# Power_and_Regulator.net
KiCad netlist of a schematic drawn in Altium Designer
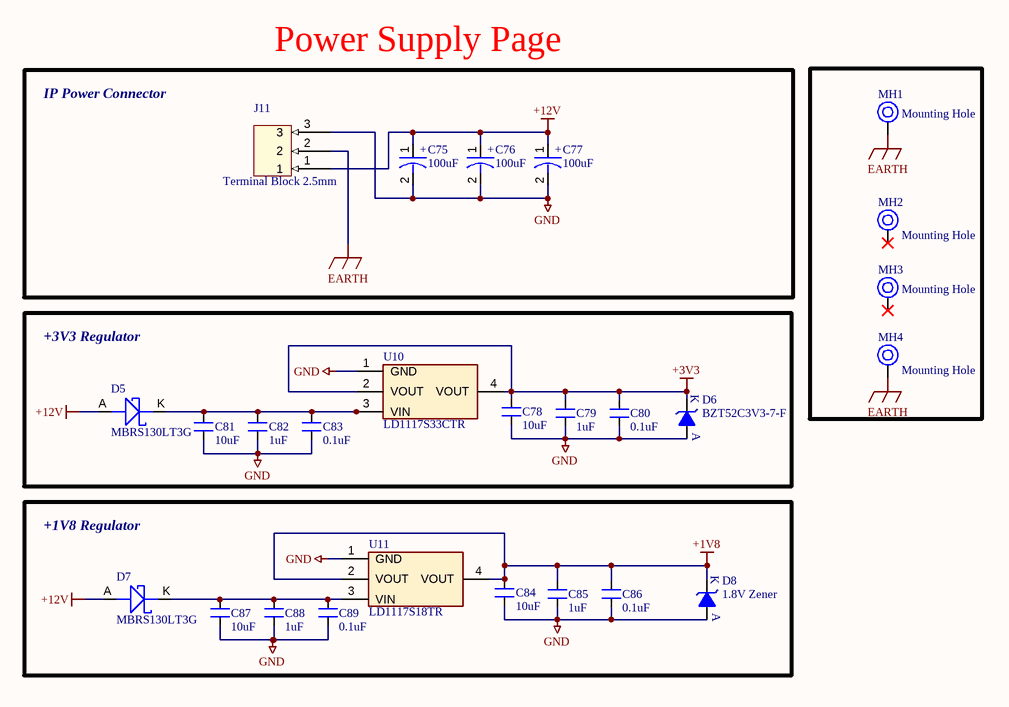
[diagram p0: Power and Regulator.SchDoc]

(export (version "E")
  (design (tool "Eeschema 10.0.6"))
  (components
    (comp (ref "C75")
      (value "100uF")
      (footprint "ACAP_P305_D393_H393_RAD")
      (description "100µF 50V Aluminum Polymer Capacitor Radial, Can - SMD 28mOhm 4000 Hrs @ 125°C")
      (fields
        (field (name "MANUFACTURER") "Nichicon")
        (field (name "MANUFACTURER PART NUMBER") "GYA1H101MCQ1GS")
      )
      (libsource (lib "ESTEEMPCBLIB") (part "CAP-P_100uF-50V-20%-RAD"))
    )
    (comp (ref "C76")
      (value "100uF")
      (footprint "ACAP_P305_D393_H393_RAD")
      (description "100µF 50V Aluminum Polymer Capacitor Radial, Can - SMD 28mOhm 4000 Hrs @ 125°C")
      (fields
        (field (name "MANUFACTURER") "Nichicon")
        (field (name "MANUFACTURER PART NUMBER") "GYA1H101MCQ1GS")
      )
      (libsource (lib "ESTEEMPCBLIB") (part "CAP-P_100uF-50V-20%-RAD"))
    )
    (comp (ref "C77")
      (value "100uF")
      (footprint "ACAP_P305_D393_H393_RAD")
      (description "100µF 50V Aluminum Polymer Capacitor Radial, Can - SMD 28mOhm 4000 Hrs @ 125°C")
      (fields
        (field (name "MANUFACTURER") "Nichicon")
        (field (name "MANUFACTURER PART NUMBER") "GYA1H101MCQ1GS")
      )
      (libsource (lib "ESTEEMPCBLIB") (part "CAP-P_100uF-50V-20%-RAD"))
    )
    (comp (ref "C78")
      (value "10uF")
      (footprint "CAP_1206")
      (description "10µF ±10% 50V Ceramic Capacitor X7R 1206 (3216 Metric)")
      (fields
        (field (name "MANUFACTURER") "KEMET")
        (field (name "MANUFACTURER PART NUMBER") "CL31B106KBHNNNE")
      )
      (libsource (lib "ESTEEMPCBLIB") (part "CAP_10uF-50V-10%-1206"))
    )
    (comp (ref "C79")
      (value "1uF")
      (footprint "CAP_0805")
      (description "1µF ±5% 50V Ceramic Capacitor X7R 0805 (2012 Metric)")
      (fields
        (field (name "MANUFACTURER") "Samsung")
        (field (name "MANUFACTURER PART NUMBER") "CC0805JKX7R9BB105")
      )
      (libsource (lib "ESTEEMPCBLIB") (part "CAP_1uF-50V-5%-0805"))
    )
    (comp (ref "C80")
      (value "0.1uF")
      (footprint "CAP_0805")
      (description "0.1µF ±20% 50V Ceramic Capacitor X7R 0805 (2012 Metric)")
      (fields
        (field (name "MANUFACTURER") "Samsung Electro-Mechanics")
        (field (name "MANUFACTURER PART NUMBER") "CL21B104MBCNNNC")
      )
      (libsource (lib "ESTEEMPCBLIB") (part "CAP_0.1uF-50V-20%-0805"))
    )
    (comp (ref "C81")
      (value "10uF")
      (footprint "CAP_1206")
      (description "10µF ±10% 50V Ceramic Capacitor X7R 1206 (3216 Metric)")
      (fields
        (field (name "MANUFACTURER") "KEMET")
        (field (name "MANUFACTURER PART NUMBER") "CL31B106KBHNNNE")
      )
      (libsource (lib "ESTEEMPCBLIB") (part "CAP_10uF-50V-10%-1206"))
    )
    (comp (ref "C82")
      (value "1uF")
      (footprint "CAP_0805")
      (description "1µF ±5% 50V Ceramic Capacitor X7R 0805 (2012 Metric)")
      (fields
        (field (name "MANUFACTURER") "Samsung")
        (field (name "MANUFACTURER PART NUMBER") "CC0805JKX7R9BB105")
      )
      (libsource (lib "ESTEEMPCBLIB") (part "CAP_1uF-50V-5%-0805"))
    )
    (comp (ref "C83")
      (value "0.1uF")
      (footprint "CAP_0805")
      (description "0.1µF ±20% 50V Ceramic Capacitor X7R 0805 (2012 Metric)")
      (fields
        (field (name "MANUFACTURER") "Samsung Electro-Mechanics")
        (field (name "MANUFACTURER PART NUMBER") "CL21B104MBCNNNC")
      )
      (libsource (lib "ESTEEMPCBLIB") (part "CAP_0.1uF-50V-20%-0805"))
    )
    (comp (ref "C84")
      (value "10uF")
      (footprint "CAP_1206")
      (description "10µF ±10% 50V Ceramic Capacitor X7R 1206 (3216 Metric)")
      (fields
        (field (name "MANUFACTURER") "KEMET")
        (field (name "MANUFACTURER PART NUMBER") "CL31B106KBHNNNE")
      )
      (libsource (lib "ESTEEMPCBLIB") (part "CAP_10uF-50V-10%-1206"))
    )
    (comp (ref "C85")
      (value "1uF")
      (footprint "CAP_0805")
      (description "1µF ±5% 50V Ceramic Capacitor X7R 0805 (2012 Metric)")
      (fields
        (field (name "MANUFACTURER") "Samsung")
        (field (name "MANUFACTURER PART NUMBER") "CC0805JKX7R9BB105")
      )
      (libsource (lib "ESTEEMPCBLIB") (part "CAP_1uF-50V-5%-0805"))
    )
    (comp (ref "C86")
      (value "0.1uF")
      (footprint "CAP_0805")
      (description "0.1µF ±20% 50V Ceramic Capacitor X7R 0805 (2012 Metric)")
      (fields
        (field (name "MANUFACTURER") "Samsung Electro-Mechanics")
        (field (name "MANUFACTURER PART NUMBER") "CL21B104MBCNNNC")
      )
      (libsource (lib "ESTEEMPCBLIB") (part "CAP_0.1uF-50V-20%-0805"))
    )
    (comp (ref "C87")
      (value "10uF")
      (footprint "CAP_1206")
      (description "10µF ±10% 50V Ceramic Capacitor X7R 1206 (3216 Metric)")
      (fields
        (field (name "MANUFACTURER") "KEMET")
        (field (name "MANUFACTURER PART NUMBER") "CL31B106KBHNNNE")
      )
      (libsource (lib "ESTEEMPCBLIB") (part "CAP_10uF-50V-10%-1206"))
    )
    (comp (ref "C88")
      (value "1uF")
      (footprint "CAP_0805")
      (description "1µF ±5% 50V Ceramic Capacitor X7R 0805 (2012 Metric)")
      (fields
        (field (name "MANUFACTURER") "Samsung")
        (field (name "MANUFACTURER PART NUMBER") "CC0805JKX7R9BB105")
      )
      (libsource (lib "ESTEEMPCBLIB") (part "CAP_1uF-50V-5%-0805"))
    )
    (comp (ref "C89")
      (value "0.1uF")
      (footprint "CAP_0805")
      (description "0.1µF ±20% 50V Ceramic Capacitor X7R 0805 (2012 Metric)")
      (fields
        (field (name "MANUFACTURER") "Samsung Electro-Mechanics")
        (field (name "MANUFACTURER PART NUMBER") "CL21B104MBCNNNC")
      )
      (libsource (lib "ESTEEMPCBLIB") (part "CAP_0.1uF-50V-20%-0805"))
    )
    (comp (ref "D5")
      (value "MBRS130LT3G")
      (footprint "DIO_SMB_DO-214AA")
      (description "Diode Schottky 30V 2A Surface Mount SMB")
      (fields (field (name "MANUFACTURER") "ON Semiconductor"))
      (libsource (lib "ESTEEMPCBLIB") (part "DIO-S_445mV-30V-2A-SMB"))
    )
    (comp (ref "D6")
      (value "BZT52C3V3-7-F")
      (footprint "DIO_SOD-123")
      (description "Zener Diode 3.3V 500mW ±6% Surface Mount SOD-123")
      (fields (field (name "MANUFACTURER") "Diodes Incorporated"))
      (libsource (lib "ESTEEMPCBLIB") (part "DIO-Z_3.3V-500mW-SOD123"))
    )
    (comp (ref "D7")
      (value "MBRS130LT3G")
      (footprint "DIO_SMB_DO-214AA")
      (description "Diode Schottky 30V 2A Surface Mount SMB")
      (fields (field (name "MANUFACTURER") "ON Semiconductor"))
      (libsource (lib "ESTEEMPCBLIB") (part "DIO-S_445mV-30V-2A-SMB"))
    )
    (comp (ref "D8")
      (value "1.8V Zener")
      (footprint "DIO_DO-213AB_SMD")
      (description "Zener Diode 1.8V 500mW ±5% Surface Mount DO-213AA")
      (libsource (lib "ESTEEMPCBLIB") (part "DIO-Z_1.8V-500mW-DO213AA"))
    )
    (comp (ref "J11")
      (value "Terminal Block 2.5mm")
      (footprint "CON3_100_TB_TH_ST")
      (description "3 Pins, 1 Row 2.54mm Pitch, straight Connector, male")
      (fields
        (field (name "MANUFACTURER PART NUMBER") "1725669")
        (field (name "MANUFACTURER") "Phoenix Contact")
      )
      (libsource (lib "ESTEEMPCBLIB") (part "CON-TB_3X1-100-ST-TH"))
    )
    (comp (ref "MH1")
      (value "Mounting Hole")
      (footprint "MOUNTING")
      (fields (field (name "MANUFACTURER PART NUMBER") "NA"))
      (libsource (lib "ESTEEMPCBLIB") (part "MH_3.5H_6D"))
    )
    (comp (ref "MH2")
      (value "Mounting Hole")
      (footprint "MOUNTING")
      (fields (field (name "MANUFACTURER PART NUMBER") "NA"))
      (libsource (lib "ESTEEMPCBLIB") (part "MH_3.5H_6D"))
    )
    (comp (ref "MH3")
      (value "Mounting Hole")
      (footprint "MOUNTING")
      (fields (field (name "MANUFACTURER PART NUMBER") "NA"))
      (libsource (lib "ESTEEMPCBLIB") (part "MH_3.5H_6D"))
    )
    (comp (ref "MH4")
      (value "Mounting Hole")
      (footprint "MOUNTING")
      (fields (field (name "MANUFACTURER PART NUMBER") "NA"))
      (libsource (lib "ESTEEMPCBLIB") (part "MH_3.5H_6D"))
    )
    (comp (ref "U10")
      (value "LD1117S33CTR")
      (footprint "SOT223_3")
      (description "Linear Voltage Regulator IC 1 Output 800mA SOT-223")
      (fields (field (name "MANUFACTURER") "STMicroelectronics"))
      (libsource (lib "ESTEEMPCBLIB") (part "REG_15V-3.3V-0.9A-12W-SOT223"))
    )
    (comp (ref "U11")
      (value "LD1117S18TR")
      (footprint "SOT223_3")
      (description "LDO Voltage Regulators 1.8V 0.8A Positive")
      (fields (field (name "MANUFACTURER") "STMicroelectronics"))
      (libsource (lib "ESTEEMPCBLIB") (part "REG_15V-1.8V-0.8A-1.4W-SOT223"))
    )
  )
  (nets
    (net (code "1") (name "+1V8") (class "Default")
      (node (ref "C84") (pin "2") (pinfunction "2_2") (pintype "passive"))
      (node (ref "C85") (pin "2") (pinfunction "2_2") (pintype "passive"))
      (node (ref "C86") (pin "2") (pinfunction "2_2") (pintype "passive"))
      (node (ref "D8") (pin "K") (pinfunction "K_K") (pintype "passive"))
      (node (ref "U11") (pin "2") (pinfunction "VOUT_2") (pintype "passive"))
      (node (ref "U11") (pin "4") (pinfunction "VOUT_4") (pintype "passive"))
    )
    (net (code "2") (name "+3V3") (class "Default")
      (node (ref "C78") (pin "2") (pinfunction "2_2") (pintype "passive"))
      (node (ref "C79") (pin "2") (pinfunction "2_2") (pintype "passive"))
      (node (ref "C80") (pin "2") (pinfunction "2_2") (pintype "passive"))
      (node (ref "D6") (pin "K") (pinfunction "K_K") (pintype "passive"))
      (node (ref "U10") (pin "2") (pinfunction "VOUT_2") (pintype "passive"))
      (node (ref "U10") (pin "4") (pinfunction "VOUT_4") (pintype "passive"))
    )
    (net (code "3") (name "+12V") (class "Default")
      (node (ref "C75") (pin "1") (pinfunction "1_1") (pintype "passive"))
      (node (ref "C76") (pin "1") (pinfunction "1_1") (pintype "passive"))
      (node (ref "C77") (pin "1") (pinfunction "1_1") (pintype "passive"))
      (node (ref "D5") (pin "A") (pinfunction "A_A") (pintype "passive"))
      (node (ref "D7") (pin "A") (pinfunction "A_A") (pintype "passive"))
      (node (ref "J11") (pin "1") (pinfunction "1_1") (pintype "input"))
    )
    (net (code "4") (name "EARTH") (class "Default")
      (node (ref "J11") (pin "2") (pinfunction "2_2") (pintype "input"))
      (node (ref "MH1") (pin "1") (pinfunction "1_1") (pintype "passive"))
      (node (ref "MH4") (pin "1") (pinfunction "1_1") (pintype "passive"))
    )
    (net (code "5") (name "GND") (class "Default")
      (node (ref "C75") (pin "2") (pinfunction "2_2") (pintype "passive"))
      (node (ref "C76") (pin "2") (pinfunction "2_2") (pintype "passive"))
      (node (ref "C77") (pin "2") (pinfunction "2_2") (pintype "passive"))
      (node (ref "C78") (pin "1") (pinfunction "1_1") (pintype "passive"))
      (node (ref "C79") (pin "1") (pinfunction "1_1") (pintype "passive"))
      (node (ref "C80") (pin "1") (pinfunction "1_1") (pintype "passive"))
      (node (ref "C81") (pin "1") (pinfunction "1_1") (pintype "passive"))
      (node (ref "C82") (pin "1") (pinfunction "1_1") (pintype "passive"))
      (node (ref "C83") (pin "1") (pinfunction "1_1") (pintype "passive"))
      (node (ref "C84") (pin "1") (pinfunction "1_1") (pintype "passive"))
      (node (ref "C85") (pin "1") (pinfunction "1_1") (pintype "passive"))
      (node (ref "C86") (pin "1") (pinfunction "1_1") (pintype "passive"))
      (node (ref "C87") (pin "1") (pinfunction "1_1") (pintype "passive"))
      (node (ref "C88") (pin "1") (pinfunction "1_1") (pintype "passive"))
      (node (ref "C89") (pin "1") (pinfunction "1_1") (pintype "passive"))
      (node (ref "D6") (pin "A") (pinfunction "A_A") (pintype "passive"))
      (node (ref "D8") (pin "A") (pinfunction "A_A") (pintype "passive"))
      (node (ref "J11") (pin "3") (pinfunction "3_3") (pintype "input"))
      (node (ref "U10") (pin "1") (pinfunction "GND_1") (pintype "passive"))
      (node (ref "U11") (pin "1") (pinfunction "GND_1") (pintype "passive"))
    )
    (net (code "6") (name "Net-(U10-VIN)") (class "Default")
      (node (ref "C81") (pin "2") (pinfunction "2_2") (pintype "passive"))
      (node (ref "C82") (pin "2") (pinfunction "2_2") (pintype "passive"))
      (node (ref "C83") (pin "2") (pinfunction "2_2") (pintype "passive"))
      (node (ref "D5") (pin "K") (pinfunction "K_K") (pintype "passive"))
      (node (ref "U10") (pin "3") (pinfunction "VIN_3") (pintype "passive"))
    )
    (net (code "7") (name "Net-(U11-VIN)") (class "Default")
      (node (ref "C87") (pin "2") (pinfunction "2_2") (pintype "passive"))
      (node (ref "C88") (pin "2") (pinfunction "2_2") (pintype "passive"))
      (node (ref "C89") (pin "2") (pinfunction "2_2") (pintype "passive"))
      (node (ref "D7") (pin "K") (pinfunction "K_K") (pintype "passive"))
      (node (ref "U11") (pin "3") (pinfunction "VIN_3") (pintype "passive"))
    )
    (net (code "8") (name "unconnected-(MH2-Pad1)") (class "Default")
      (node (ref "MH2") (pin "1") (pinfunction "1_1") (pintype "passive+no_connect"))
    )
    (net (code "9") (name "unconnected-(MH3-Pad1)") (class "Default")
      (node (ref "MH3") (pin "1") (pinfunction "1_1") (pintype "passive+no_connect"))
    )
  )
)
